# main.net
KiCad netlist of a schematic drawn in EAGLE
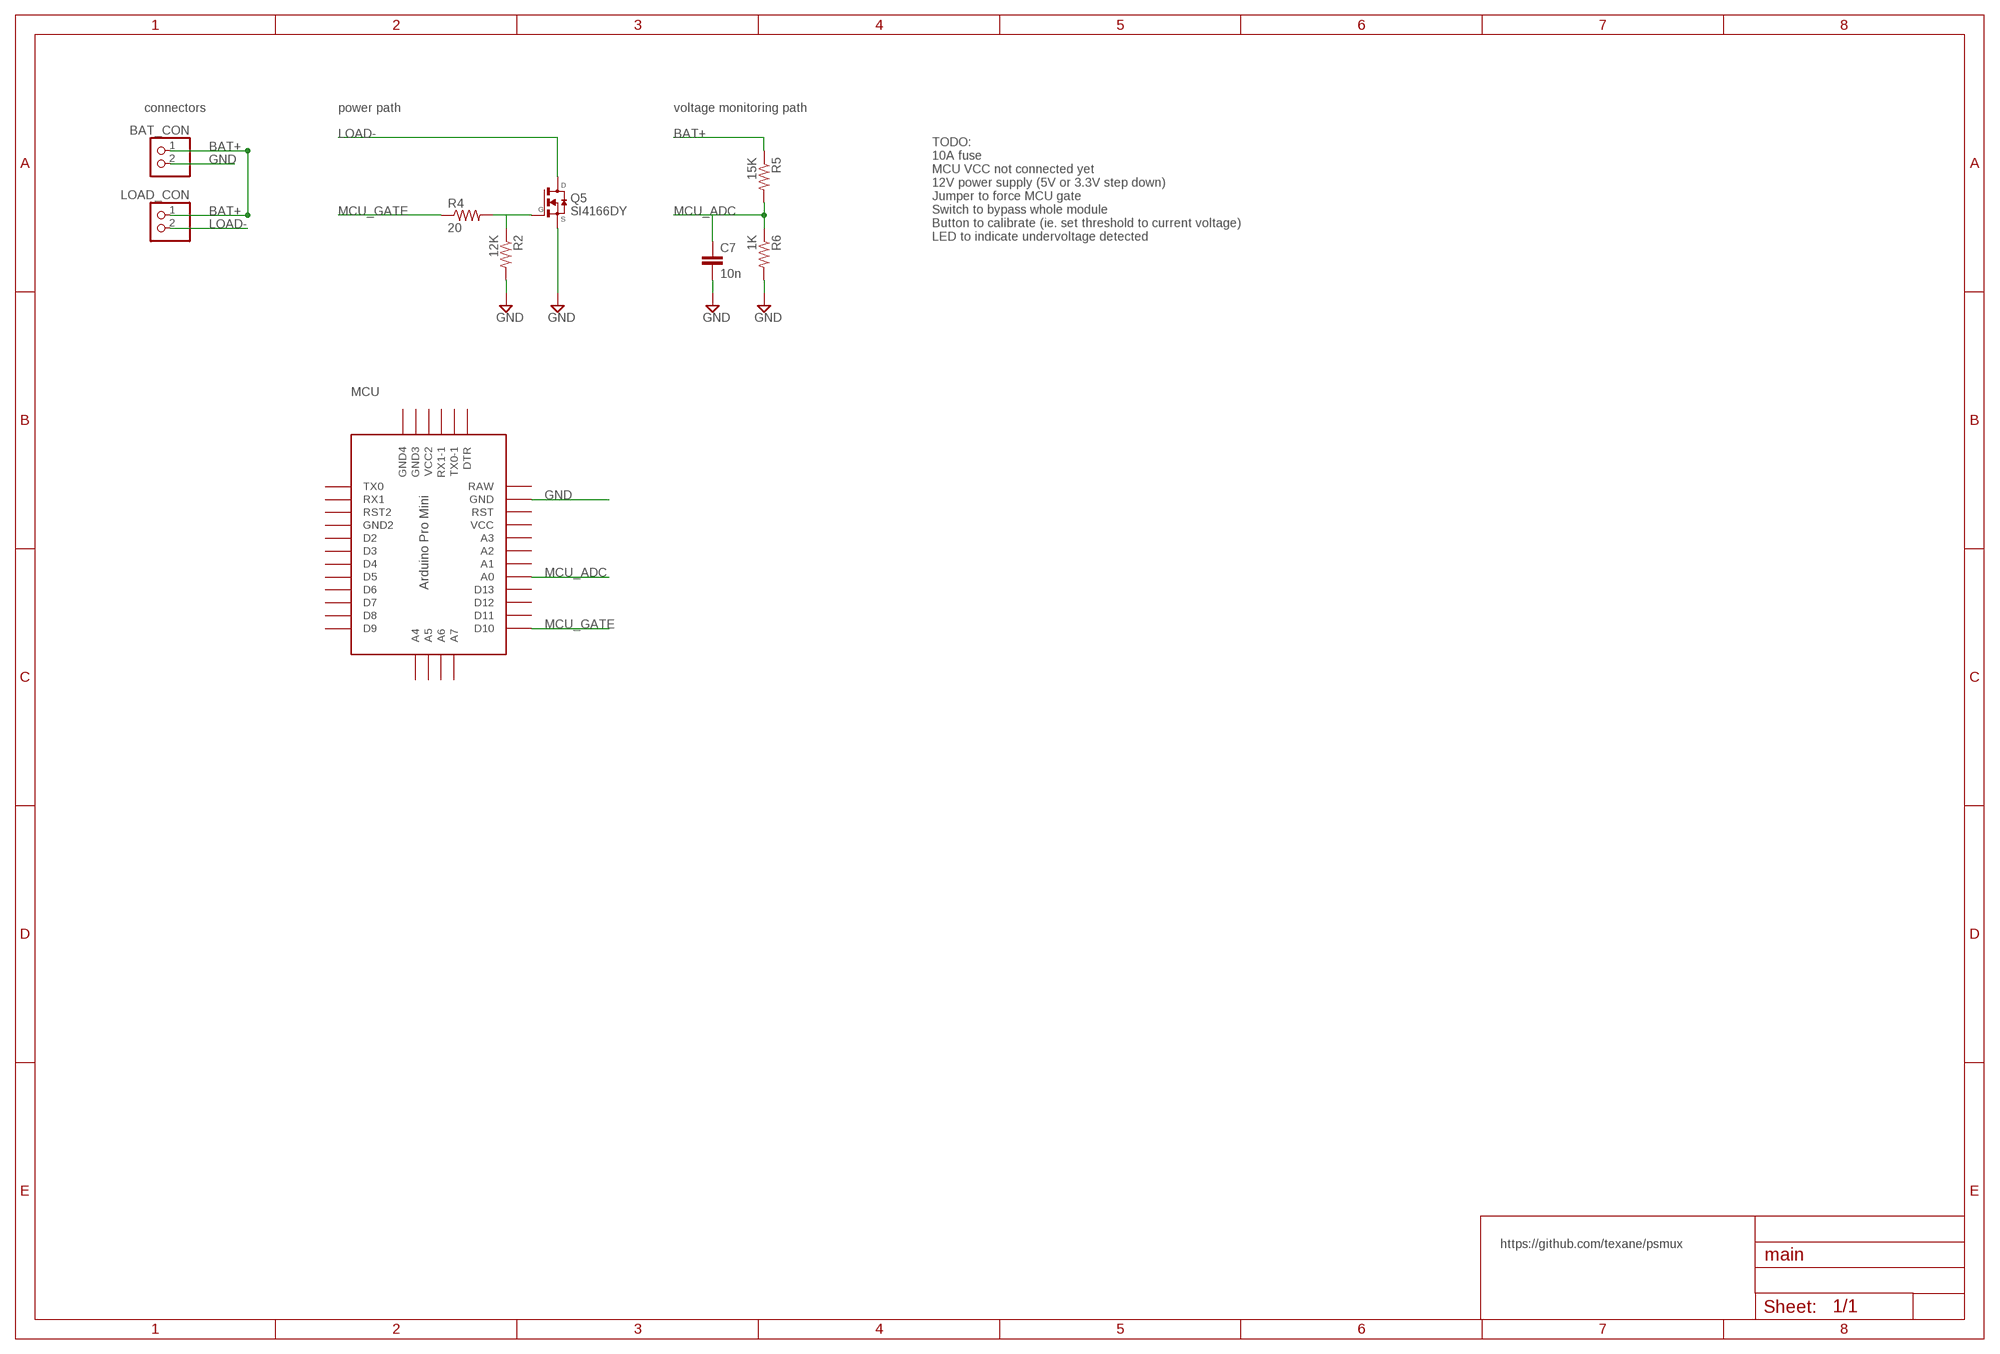
[diagram p0: schematic, sheet 1]

(export (version "E")
  (design (tool "Eeschema 10.0.6"))
  (components
    (comp (ref "BAT_CON")
      (value "PINHD-1X2")
      (footprint "eagle-import:1X02")
      (libsource (lib "eagle-import") (part "PINHD-1X2"))
    )
    (comp (ref "C7")
      (value "10n")
      (footprint "eagle-import:C0805K")
      (libsource (lib "eagle-import") (part "C-EUC0805K"))
    )
    (comp (ref "LOAD_CON")
      (value "PINHD-1X2")
      (footprint "eagle-import:1X02")
      (libsource (lib "eagle-import") (part "PINHD-1X2"))
    )
    (comp (ref "Q5")
      (value "SI4840DY")
      (footprint "eagle-import:SO08-E3")
      (libsource (lib "eagle-import") (part "SI4840DY"))
    )
    (comp (ref "R2")
      (value "12K")
      (footprint "eagle-import:M0805")
      (libsource (lib "eagle-import") (part "R-US_M0805"))
    )
    (comp (ref "R4")
      (value "20")
      (footprint "eagle-import:M0805")
      (libsource (lib "eagle-import") (part "R-US_M0805"))
    )
    (comp (ref "R5")
      (value "15K")
      (footprint "eagle-import:M0805")
      (libsource (lib "eagle-import") (part "R-US_M0805"))
    )
    (comp (ref "R6")
      (value "1K")
      (footprint "eagle-import:M0805")
      (libsource (lib "eagle-import") (part "R-US_M0805"))
    )
    (comp (ref "U$1")
      (value "PRO-MINI")
      (footprint "eagle-import:PRO-MINI")
      (libsource (lib "eagle-import") (part "PRO-MINI"))
    )
  )
  (nets
    (net (code "1") (name "/BAT+") (class "Default")
      (node (ref "BAT_CON") (pin "1") (pinfunction "1_1") (pintype "passive"))
      (node (ref "LOAD_CON") (pin "1") (pinfunction "1_1") (pintype "passive"))
      (node (ref "R5") (pin "1") (pinfunction "1_1") (pintype "passive"))
    )
    (net (code "2") (name "/LOAD-") (class "Default")
      (node (ref "LOAD_CON") (pin "2") (pinfunction "2_2") (pintype "passive"))
      (node (ref "Q5") (pin "5-8") (pinfunction "D_5-8") (pintype "passive"))
    )
    (net (code "3") (name "/MCU_ADC") (class "Default")
      (node (ref "C7") (pin "1") (pinfunction "1_1") (pintype "passive"))
      (node (ref "R5") (pin "2") (pinfunction "2_2") (pintype "passive"))
      (node (ref "R6") (pin "1") (pinfunction "1_1") (pintype "passive"))
      (node (ref "U$1") (pin "A0") (pinfunction "A0_A0") (pintype "bidirectional"))
    )
    (net (code "4") (name "/MCU_GATE") (class "Default")
      (node (ref "R4") (pin "1") (pinfunction "1_1") (pintype "passive"))
      (node (ref "U$1") (pin "D10") (pinfunction "D10_D10") (pintype "bidirectional"))
    )
    (net (code "5") (name "/RAW") (class "Default")
      (node (ref "U$1") (pin "RAW") (pinfunction "RAW_RAW") (pintype "power_in"))
    )
    (net (code "6") (name "GND") (class "Default")
      (node (ref "BAT_CON") (pin "2") (pinfunction "2_2") (pintype "passive"))
      (node (ref "C7") (pin "2") (pinfunction "2_2") (pintype "passive"))
      (node (ref "Q5") (pin "1-3") (pinfunction "S_1-3") (pintype "passive"))
      (node (ref "R2") (pin "2") (pinfunction "2_2") (pintype "passive"))
      (node (ref "R6") (pin "2") (pinfunction "2_2") (pintype "passive"))
      (node (ref "U$1") (pin "GND") (pinfunction "GND_GND") (pintype "input"))
    )
    (net (code "7") (name "Net-(Q5-G)") (class "Default")
      (node (ref "Q5") (pin "4") (pinfunction "G_4") (pintype "passive"))
      (node (ref "R2") (pin "1") (pinfunction "1_1") (pintype "passive"))
      (node (ref "R4") (pin "2") (pinfunction "2_2") (pintype "passive"))
    )
    (net (code "8") (name "unconnected-(U$1-GND2-PadGND1)") (class "Default")
      (node (ref "U$1") (pin "GND1") (pinfunction "GND2_GND1") (pintype "bidirectional"))
    )
    (net (code "9") (name "unconnected-(U$1-GND4-PadGND2)") (class "Default")
      (node (ref "U$1") (pin "GND2") (pinfunction "GND4_GND2") (pintype "bidirectional"))
    )
    (net (code "10") (name "unconnected-(U$1-PadA1)") (class "Default")
      (node (ref "U$1") (pin "A1") (pinfunction "A1_A1") (pintype "bidirectional"))
    )
    (net (code "11") (name "unconnected-(U$1-PadA2)") (class "Default")
      (node (ref "U$1") (pin "A2") (pinfunction "A2_A2") (pintype "bidirectional"))
    )
    (net (code "12") (name "unconnected-(U$1-PadA3)") (class "Default")
      (node (ref "U$1") (pin "A3") (pinfunction "A3_A3") (pintype "bidirectional"))
    )
    (net (code "13") (name "unconnected-(U$1-PadA4)") (class "Default")
      (node (ref "U$1") (pin "A4") (pinfunction "A4_A4") (pintype "bidirectional"))
    )
    (net (code "14") (name "unconnected-(U$1-PadA5)") (class "Default")
      (node (ref "U$1") (pin "A5") (pinfunction "A5_A5") (pintype "bidirectional"))
    )
    (net (code "15") (name "unconnected-(U$1-PadA6)") (class "Default")
      (node (ref "U$1") (pin "A6") (pinfunction "A6_A6") (pintype "bidirectional"))
    )
    (net (code "16") (name "unconnected-(U$1-PadA7)") (class "Default")
      (node (ref "U$1") (pin "A7") (pinfunction "A7_A7") (pintype "bidirectional"))
    )
    (net (code "17") (name "unconnected-(U$1-PadD2)") (class "Default")
      (node (ref "U$1") (pin "D2") (pinfunction "D2_D2") (pintype "bidirectional"))
    )
    (net (code "18") (name "unconnected-(U$1-PadD3)") (class "Default")
      (node (ref "U$1") (pin "D3") (pinfunction "D3_D3") (pintype "bidirectional"))
    )
    (net (code "19") (name "unconnected-(U$1-PadD4)") (class "Default")
      (node (ref "U$1") (pin "D4") (pinfunction "D4_D4") (pintype "bidirectional"))
    )
    (net (code "20") (name "unconnected-(U$1-PadD5)") (class "Default")
      (node (ref "U$1") (pin "D5") (pinfunction "D5_D5") (pintype "bidirectional"))
    )
    (net (code "21") (name "unconnected-(U$1-PadD6)") (class "Default")
      (node (ref "U$1") (pin "D6") (pinfunction "D6_D6") (pintype "bidirectional"))
    )
    (net (code "22") (name "unconnected-(U$1-PadD7)") (class "Default")
      (node (ref "U$1") (pin "D7") (pinfunction "D7_D7") (pintype "bidirectional"))
    )
    (net (code "23") (name "unconnected-(U$1-PadD8)") (class "Default")
      (node (ref "U$1") (pin "D8") (pinfunction "D8_D8") (pintype "bidirectional"))
    )
    (net (code "24") (name "unconnected-(U$1-PadD9)") (class "Default")
      (node (ref "U$1") (pin "D9") (pinfunction "D9_D9") (pintype "bidirectional"))
    )
    (net (code "25") (name "unconnected-(U$1-PadD11)") (class "Default")
      (node (ref "U$1") (pin "D11") (pinfunction "D11_D11") (pintype "bidirectional"))
    )
    (net (code "26") (name "unconnected-(U$1-PadD12)") (class "Default")
      (node (ref "U$1") (pin "D12") (pinfunction "D12_D12") (pintype "bidirectional"))
    )
    (net (code "27") (name "unconnected-(U$1-PadD13)") (class "Default")
      (node (ref "U$1") (pin "D13") (pinfunction "D13_D13") (pintype "bidirectional"))
    )
    (net (code "28") (name "unconnected-(U$1-PadDTR)") (class "Default")
      (node (ref "U$1") (pin "DTR") (pinfunction "DTR_DTR") (pintype "bidirectional"))
    )
    (net (code "29") (name "unconnected-(U$1-PadGND3)") (class "Default")
      (node (ref "U$1") (pin "GND3") (pinfunction "GND3_GND3") (pintype "bidirectional"))
    )
    (net (code "30") (name "unconnected-(U$1-PadRST)") (class "Default")
      (node (ref "U$1") (pin "RST") (pinfunction "RST_RST") (pintype "bidirectional"))
    )
    (net (code "31") (name "unconnected-(U$1-PadRX1)") (class "Default")
      (node (ref "U$1") (pin "RX1") (pinfunction "RX1_RX1") (pintype "bidirectional"))
    )
    (net (code "32") (name "unconnected-(U$1-PadRX1-1)") (class "Default")
      (node (ref "U$1") (pin "RX1-1") (pinfunction "RX1-1_RX1-1") (pintype "bidirectional"))
    )
    (net (code "33") (name "unconnected-(U$1-PadTX0)") (class "Default")
      (node (ref "U$1") (pin "TX0") (pinfunction "TX0_TX0") (pintype "bidirectional"))
    )
    (net (code "34") (name "unconnected-(U$1-PadTX0-1)") (class "Default")
      (node (ref "U$1") (pin "TX0-1") (pinfunction "TX0-1_TX0-1") (pintype "bidirectional"))
    )
    (net (code "35") (name "unconnected-(U$1-PadVCC)") (class "Default")
      (node (ref "U$1") (pin "VCC") (pinfunction "VCC_VCC") (pintype "bidirectional"))
    )
    (net (code "36") (name "unconnected-(U$1-RST2-PadRST1)") (class "Default")
      (node (ref "U$1") (pin "RST1") (pinfunction "RST2_RST1") (pintype "bidirectional"))
    )
    (net (code "37") (name "unconnected-(U$1-VCC2-PadVCC1)") (class "Default")
      (node (ref "U$1") (pin "VCC1") (pinfunction "VCC2_VCC1") (pintype "bidirectional"))
    )
  )
)
